# SiPM_Array_v3.net
KiCad netlist of a schematic drawn in Altium Designer
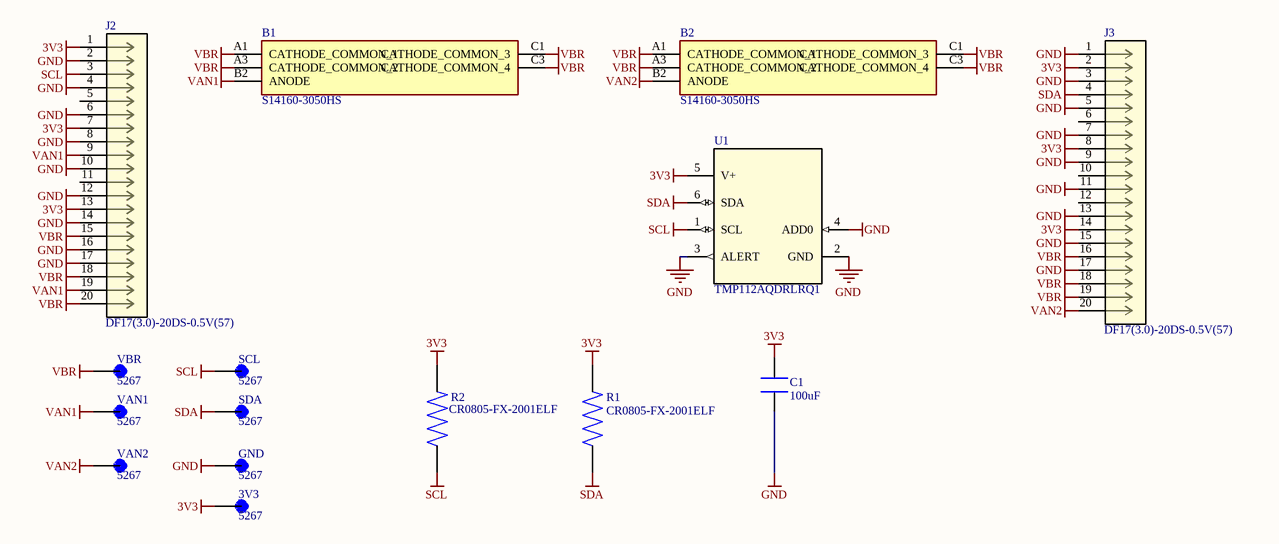
[diagram p0: SiPM_Array_v3.SchDoc]

(export (version "E")
  (design (tool "Eeschema 10.0.6"))
  (components
    (comp (ref "3V3")
      (value "5267")
      (footprint "KEYSTONE_5267")
      (description "TEST POINT (BLUE) - MINIATURE")
      (fields (field (name "MF") "Keystone Electronics"))
      (libsource (lib "5267") (part "5267"))
    )
    (comp (ref "B1")
      (value "S14160-3050HS")
      (footprint "S141603050HS")
      (libsource (lib "S14160-3050HS") (part "S14160-3050HS"))
    )
    (comp (ref "B2")
      (value "S14160-3050HS")
      (footprint "S141603050HS")
      (libsource (lib "S14160-3050HS") (part "S14160-3050HS"))
    )
    (comp (ref "C1")
      (value "100uF")
      (footprint "APSS Flight Parts:CAPACITOR_0805_2012M-70N")
      (fields
        (field (name "TOLERANCE") "±20%")
        (field (name "MF PART NO.") "GRM21BR60J107ME15L")
        (field (name "APSS STANDARD PART") "APSS Standard")
      )
      (libsource (lib "APSS Flight Parts") (part "GRM21BR60J107ME15L"))
    )
    (comp (ref "GND")
      (value "5267")
      (footprint "KEYSTONE_5267")
      (description "TEST POINT (BLUE) - MINIATURE")
      (fields (field (name "MF") "Keystone Electronics"))
      (libsource (lib "5267") (part "5267"))
    )
    (comp (ref "J2")
      (value "DF17(3.0)-20DS-0.5V(57)")
      (footprint "CONN_DF173.0-20DS-0.5V57_HIR")
      (description "Description")
      (fields (field (name "COPYRIGHT") "Copyright (C) 2025 Ultra Librarian. All rights reserved."))
      (libsource (lib "DF173P0-20DS-0P5V57") (part "DF173.0-20DS-0.5V57"))
    )
    (comp (ref "J3")
      (value "DF17(3.0)-20DS-0.5V(57)")
      (footprint "CONN_DF173.0-20DS-0.5V57_HIR")
      (description "Description")
      (fields (field (name "COPYRIGHT") "Copyright (C) 2025 Ultra Librarian. All rights reserved."))
      (libsource (lib "DF173P0-20DS-0P5V57") (part "DF173.0-20DS-0.5V57"))
    )
    (comp (ref "R1")
      (value "CR0805-FX-2001ELF")
      (footprint "RESC2012X60N")
      (description "Res 0805 2k 1% 125mW ¦ Bourns CR0805-FX-2001ELF")
      (fields (field (name "MF") "Bourns"))
      (libsource (lib "CR0805-FX-2001ELF") (part "CR0805-FX-2001ELF"))
    )
    (comp (ref "R2")
      (value "CR0805-FX-2001ELF")
      (footprint "RESC2012X60N")
      (description "Res 0805 2k 1% 125mW ¦ Bourns CR0805-FX-2001ELF")
      (fields (field (name "MF") "Bourns"))
      (libsource (lib "CR0805-FX-2001ELF") (part "CR0805-FX-2001ELF"))
    )
    (comp (ref "SCL")
      (value "5267")
      (footprint "KEYSTONE_5267")
      (description "TEST POINT (BLUE) - MINIATURE")
      (fields (field (name "MF") "Keystone Electronics"))
      (libsource (lib "5267") (part "5267"))
    )
    (comp (ref "SDA")
      (value "5267")
      (footprint "KEYSTONE_5267")
      (description "TEST POINT (BLUE) - MINIATURE")
      (fields (field (name "MF") "Keystone Electronics"))
      (libsource (lib "5267") (part "5267"))
    )
    (comp (ref "U1")
      (value "TMP112AQDRLRQ1")
      (footprint "DRL0006A")
      (description "No Description Available")
      (fields (field (name "MANUFACTURER") "Texas Instruments"))
      (libsource (lib "APSS3Rad") (part "TMP112AQDRLRQ1"))
    )
    (comp (ref "VAN1")
      (value "5267")
      (footprint "KEYSTONE_5267")
      (description "TEST POINT (BLUE) - MINIATURE")
      (fields (field (name "MF") "Keystone Electronics"))
      (libsource (lib "5267") (part "5267"))
    )
    (comp (ref "VAN2")
      (value "5267")
      (footprint "KEYSTONE_5267")
      (description "TEST POINT (BLUE) - MINIATURE")
      (fields (field (name "MF") "Keystone Electronics"))
      (libsource (lib "5267") (part "5267"))
    )
    (comp (ref "VBR")
      (value "5267")
      (footprint "KEYSTONE_5267")
      (description "TEST POINT (BLUE) - MINIATURE")
      (fields (field (name "MF") "Keystone Electronics"))
      (libsource (lib "5267") (part "5267"))
    )
  )
  (nets
    (net (code "1") (name "3V3") (class "Default")
      (node (ref "3V3") (pin "TP") (pinfunction "TP_TP") (pintype "passive"))
      (node (ref "C1") (pin "2") (pinfunction "2_2") (pintype "passive"))
      (node (ref "J2") (pin "1") (pinfunction "1_1") (pintype "passive"))
      (node (ref "J2") (pin "13") (pinfunction "13_13") (pintype "passive"))
      (node (ref "J2") (pin "7") (pinfunction "7_7") (pintype "passive"))
      (node (ref "J3") (pin "14") (pinfunction "14_14") (pintype "passive"))
      (node (ref "J3") (pin "2") (pinfunction "2_2") (pintype "passive"))
      (node (ref "J3") (pin "8") (pinfunction "8_8") (pintype "passive"))
      (node (ref "R1") (pin "1") (pinfunction "1_1") (pintype "passive"))
      (node (ref "R2") (pin "1") (pinfunction "1_1") (pintype "passive"))
      (node (ref "U1") (pin "5") (pinfunction "V+_5") (pintype "power_in"))
    )
    (net (code "2") (name "GND") (class "Default")
      (node (ref "C1") (pin "1") (pinfunction "1_1") (pintype "passive"))
      (node (ref "GND") (pin "TP") (pinfunction "TP_TP") (pintype "passive"))
      (node (ref "J2") (pin "10") (pinfunction "10_10") (pintype "passive"))
      (node (ref "J2") (pin "12") (pinfunction "12_12") (pintype "passive"))
      (node (ref "J2") (pin "14") (pinfunction "14_14") (pintype "passive"))
      (node (ref "J2") (pin "16") (pinfunction "16_16") (pintype "passive"))
      (node (ref "J2") (pin "17") (pinfunction "17_17") (pintype "passive"))
      (node (ref "J2") (pin "2") (pinfunction "2_2") (pintype "passive"))
      (node (ref "J2") (pin "4") (pinfunction "4_4") (pintype "passive"))
      (node (ref "J2") (pin "6") (pinfunction "6_6") (pintype "passive"))
      (node (ref "J2") (pin "8") (pinfunction "8_8") (pintype "passive"))
      (node (ref "J3") (pin "1") (pinfunction "1_1") (pintype "passive"))
      (node (ref "J3") (pin "11") (pinfunction "11_11") (pintype "passive"))
      (node (ref "J3") (pin "13") (pinfunction "13_13") (pintype "passive"))
      (node (ref "J3") (pin "15") (pinfunction "15_15") (pintype "passive"))
      (node (ref "J3") (pin "17") (pinfunction "17_17") (pintype "passive"))
      (node (ref "J3") (pin "3") (pinfunction "3_3") (pintype "passive"))
      (node (ref "J3") (pin "5") (pinfunction "5_5") (pintype "passive"))
      (node (ref "J3") (pin "7") (pinfunction "7_7") (pintype "passive"))
      (node (ref "J3") (pin "9") (pinfunction "9_9") (pintype "passive"))
      (node (ref "U1") (pin "2") (pinfunction "GND_2") (pintype "power_in"))
      (node (ref "U1") (pin "3") (pinfunction "ALERT_3") (pintype "output"))
      (node (ref "U1") (pin "4") (pinfunction "ADD0_4") (pintype "input"))
    )
    (net (code "3") (name "SCL") (class "Default")
      (node (ref "J2") (pin "3") (pinfunction "3_3") (pintype "passive"))
      (node (ref "R2") (pin "2") (pinfunction "2_2") (pintype "passive"))
      (node (ref "SCL") (pin "TP") (pinfunction "TP_TP") (pintype "passive"))
      (node (ref "U1") (pin "1") (pinfunction "SCL_1") (pintype "bidirectional"))
    )
    (net (code "4") (name "SDA") (class "Default")
      (node (ref "J3") (pin "4") (pinfunction "4_4") (pintype "passive"))
      (node (ref "R1") (pin "2") (pinfunction "2_2") (pintype "passive"))
      (node (ref "SDA") (pin "TP") (pinfunction "TP_TP") (pintype "passive"))
      (node (ref "U1") (pin "6") (pinfunction "SDA_6") (pintype "bidirectional"))
    )
    (net (code "5") (name "VAN1") (class "Default")
      (node (ref "B1") (pin "B2") (pinfunction "ANODE_B2") (pintype "passive"))
      (node (ref "J2") (pin "19") (pinfunction "19_19") (pintype "passive"))
      (node (ref "J2") (pin "9") (pinfunction "9_9") (pintype "passive"))
      (node (ref "VAN1") (pin "TP") (pinfunction "TP_TP") (pintype "passive"))
    )
    (net (code "6") (name "VAN2") (class "Default")
      (node (ref "B2") (pin "B2") (pinfunction "ANODE_B2") (pintype "passive"))
      (node (ref "J3") (pin "20") (pinfunction "20_20") (pintype "passive"))
      (node (ref "VAN2") (pin "TP") (pinfunction "TP_TP") (pintype "passive"))
    )
    (net (code "7") (name "VBR") (class "Default")
      (node (ref "B1") (pin "A1") (pinfunction "CATHODE_COMMON_1_A1") (pintype "passive"))
      (node (ref "B1") (pin "A3") (pinfunction "CATHODE_COMMON_2_A3") (pintype "passive"))
      (node (ref "B1") (pin "C1") (pinfunction "CATHODE_COMMON_3_C1") (pintype "passive"))
      (node (ref "B1") (pin "C3") (pinfunction "CATHODE_COMMON_4_C3") (pintype "passive"))
      (node (ref "B2") (pin "A1") (pinfunction "CATHODE_COMMON_1_A1") (pintype "passive"))
      (node (ref "B2") (pin "A3") (pinfunction "CATHODE_COMMON_2_A3") (pintype "passive"))
      (node (ref "B2") (pin "C1") (pinfunction "CATHODE_COMMON_3_C1") (pintype "passive"))
      (node (ref "B2") (pin "C3") (pinfunction "CATHODE_COMMON_4_C3") (pintype "passive"))
      (node (ref "J2") (pin "15") (pinfunction "15_15") (pintype "passive"))
      (node (ref "J2") (pin "18") (pinfunction "18_18") (pintype "passive"))
      (node (ref "J2") (pin "20") (pinfunction "20_20") (pintype "passive"))
      (node (ref "J3") (pin "16") (pinfunction "16_16") (pintype "passive"))
      (node (ref "J3") (pin "18") (pinfunction "18_18") (pintype "passive"))
      (node (ref "J3") (pin "19") (pinfunction "19_19") (pintype "passive"))
      (node (ref "VBR") (pin "TP") (pinfunction "TP_TP") (pintype "passive"))
    )
    (net (code "8") (name "unconnected-(J2-Pad5)") (class "Default")
      (node (ref "J2") (pin "5") (pinfunction "5_5") (pintype "passive"))
    )
    (net (code "9") (name "unconnected-(J2-Pad11)") (class "Default")
      (node (ref "J2") (pin "11") (pinfunction "11_11") (pintype "passive"))
    )
    (net (code "10") (name "unconnected-(J3-Pad6)") (class "Default")
      (node (ref "J3") (pin "6") (pinfunction "6_6") (pintype "passive"))
    )
    (net (code "11") (name "unconnected-(J3-Pad10)") (class "Default")
      (node (ref "J3") (pin "10") (pinfunction "10_10") (pintype "passive"))
    )
    (net (code "12") (name "unconnected-(J3-Pad12)") (class "Default")
      (node (ref "J3") (pin "12") (pinfunction "12_12") (pintype "passive"))
    )
  )
)
